# Power_supply.net
KiCad netlist of a schematic drawn in Altium Designer
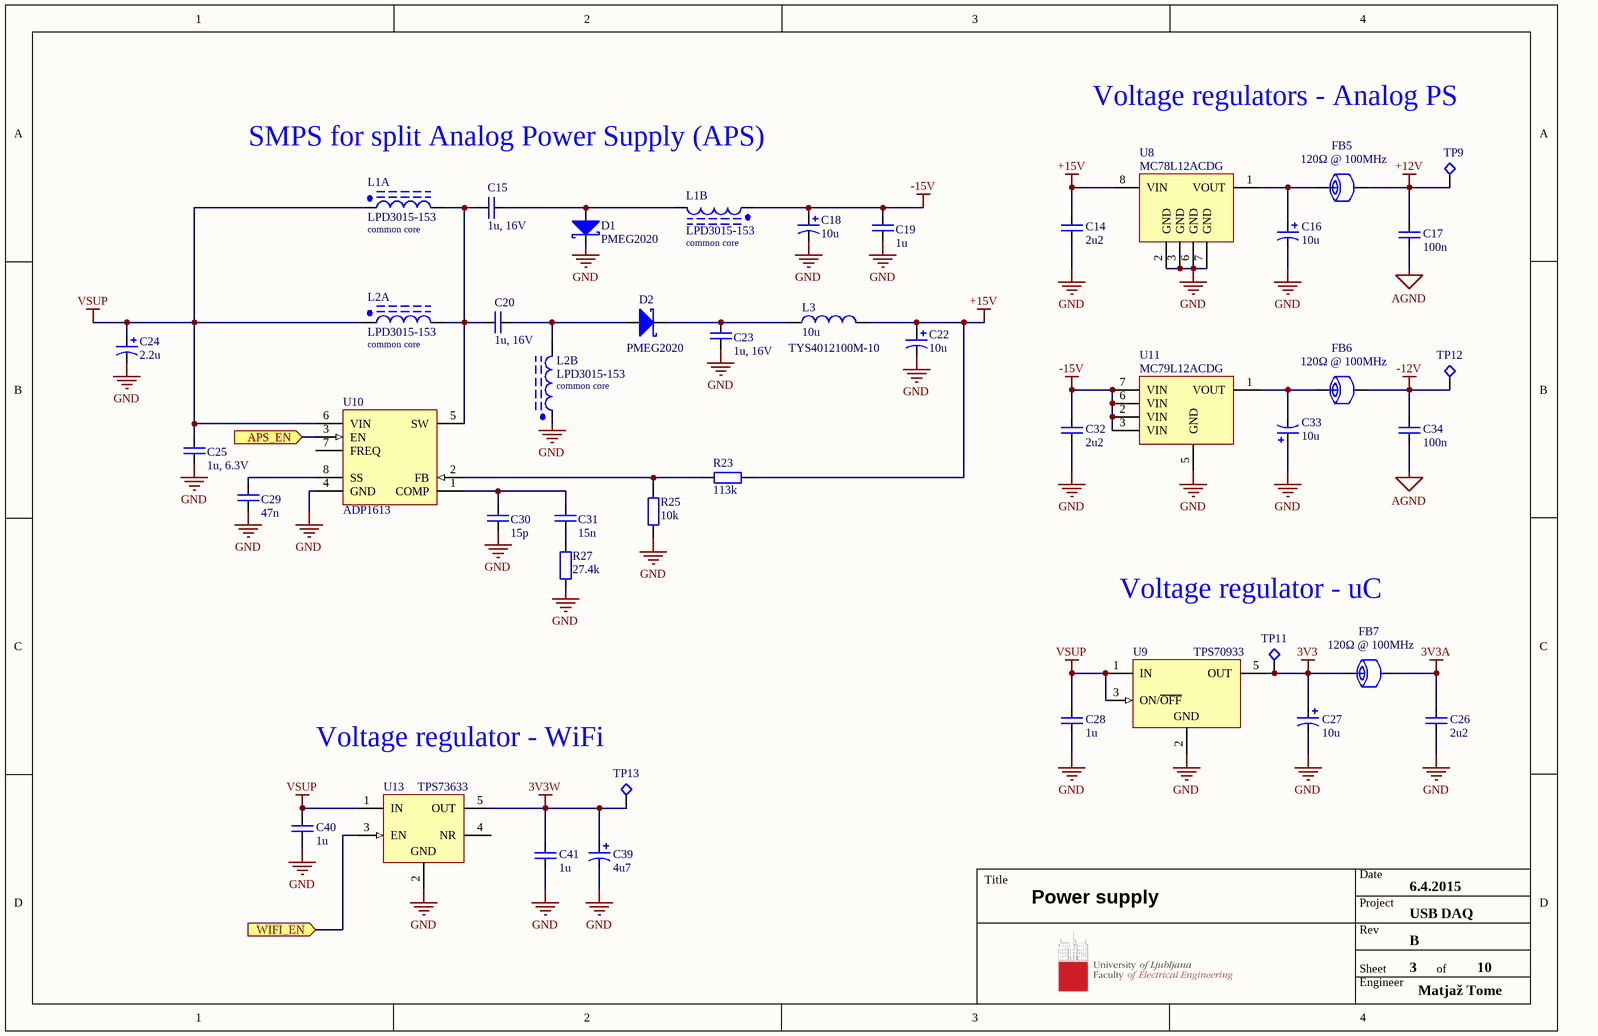
[diagram p0: Power_supply.SchDoc]

(export (version "E")
  (design (tool "Eeschema 10.0.6"))
  (components
    (comp (ref "C14")
      (value "2u2")
      (footprint "C_0603")
      (description "Generic capacitor")
      (fields (field (name "Comment") "comment"))
      (libsource (lib "DAQ") (part "Capacitor"))
    )
    (comp (ref "C15")
      (value "1u, 16V")
      (footprint "C_0603")
      (description "Generic capacitor")
      (fields (field (name "Comment") "comment"))
      (libsource (lib "DAQ") (part "Capacitor"))
    )
    (comp (ref "C16")
      (value "10u")
      (footprint "Tantalum Case A")
      (description "Generic polarized capacitor")
      (fields (field (name "Comment") "comment"))
      (libsource (lib "DAQ") (part "Capacitor - polarized"))
    )
    (comp (ref "C17")
      (value "100n")
      (footprint "C_0603")
      (description "Generic capacitor")
      (fields (field (name "Comment") "comment"))
      (libsource (lib "DAQ") (part "Capacitor"))
    )
    (comp (ref "C18")
      (value "10u")
      (footprint "Tantalum Case A")
      (description "Generic polarized capacitor")
      (fields (field (name "Comment") "comment"))
      (libsource (lib "") (part "Capacitor - polarized_1"))
    )
    (comp (ref "C19")
      (value "1u")
      (footprint "C_0603")
      (description "Generic capacitor")
      (fields (field (name "Comment") "comment"))
      (libsource (lib "DAQ") (part "Capacitor"))
    )
    (comp (ref "C20")
      (value "1u, 16V")
      (footprint "C_0603")
      (description "Generic capacitor")
      (fields (field (name "Comment") "comment"))
      (libsource (lib "DAQ") (part "Capacitor"))
    )
    (comp (ref "C22")
      (value "10u")
      (footprint "Tantalum Case A")
      (description "Generic polarized capacitor")
      (fields (field (name "Comment") "comment"))
      (libsource (lib "") (part "Capacitor - polarized_1"))
    )
    (comp (ref "C23")
      (value "1u, 16V")
      (footprint "C_0603")
      (description "Generic capacitor")
      (fields (field (name "Comment") "comment"))
      (libsource (lib "DAQ") (part "Capacitor"))
    )
    (comp (ref "C24")
      (value "2.2u")
      (footprint "Tantalum Case A")
      (description "Generic polarized capacitor")
      (fields (field (name "Comment") "comment"))
      (libsource (lib "") (part "Capacitor - polarized_1"))
    )
    (comp (ref "C25")
      (value "1u, 6.3V")
      (footprint "C_0603")
      (description "Generic capacitor")
      (fields (field (name "Comment") "comment"))
      (libsource (lib "DAQ") (part "Capacitor"))
    )
    (comp (ref "C26")
      (value "2u2")
      (footprint "C_0603")
      (description "Generic capacitor")
      (fields (field (name "Comment") "comment"))
      (libsource (lib "DAQ") (part "Capacitor"))
    )
    (comp (ref "C27")
      (value "10u")
      (footprint "Tantalum Case A")
      (description "Generic polarized capacitor")
      (fields (field (name "Comment") "comment"))
      (libsource (lib "DAQ") (part "Capacitor - polarized"))
    )
    (comp (ref "C28")
      (value "1u")
      (footprint "C_0603")
      (description "Generic capacitor")
      (fields (field (name "Comment") "comment"))
      (libsource (lib "DAQ") (part "Capacitor"))
    )
    (comp (ref "C29")
      (value "47n")
      (footprint "C_0603")
      (description "Generic capacitor")
      (fields (field (name "Comment") "comment"))
      (libsource (lib "DAQ") (part "Capacitor"))
    )
    (comp (ref "C30")
      (value "15p")
      (footprint "C_0603")
      (description "Generic capacitor")
      (fields (field (name "Comment") "comment"))
      (libsource (lib "DAQ") (part "Capacitor"))
    )
    (comp (ref "C31")
      (value "15n")
      (footprint "C_0603")
      (description "Generic capacitor")
      (fields (field (name "Comment") "comment"))
      (libsource (lib "DAQ") (part "Capacitor"))
    )
    (comp (ref "C32")
      (value "2u2")
      (footprint "C_0603")
      (description "Generic capacitor")
      (fields (field (name "Comment") "comment"))
      (libsource (lib "DAQ") (part "Capacitor"))
    )
    (comp (ref "C33")
      (value "10u")
      (footprint "Tantalum Case A")
      (description "Generic polarized capacitor")
      (fields (field (name "Comment") "comment"))
      (libsource (lib "DAQ") (part "Capacitor - polarized"))
    )
    (comp (ref "C34")
      (value "100n")
      (footprint "C_0603")
      (description "Generic capacitor")
      (fields (field (name "Comment") "comment"))
      (libsource (lib "DAQ") (part "Capacitor"))
    )
    (comp (ref "C39")
      (value "4u7")
      (footprint "Tantalum Case A")
      (description "Generic polarized capacitor")
      (fields (field (name "Comment") "comment"))
      (libsource (lib "DAQ") (part "Capacitor - polarized"))
    )
    (comp (ref "C40")
      (value "1u")
      (footprint "C_0603")
      (description "Generic capacitor")
      (fields (field (name "Comment") "comment"))
      (libsource (lib "DAQ") (part "Capacitor"))
    )
    (comp (ref "C41")
      (value "1u")
      (footprint "C_0603")
      (description "Generic capacitor")
      (fields (field (name "Comment") "comment"))
      (libsource (lib "DAQ") (part "Capacitor"))
    )
    (comp (ref "D1")
      (value "PMEG2020")
      (footprint "SOD323")
      (description "Schottky Rectifier, 20 V, 2 A, Single, SOD-323, 2 Pins, 525 mV")
      (fields (field (name "MANUFACTURER") "Infineon"))
      (libsource (lib "DAQ") (part "PMEG2020"))
    )
    (comp (ref "D2")
      (value "PMEG2020")
      (footprint "SOD323")
      (description "Schottky Rectifier, 20 V, 2 A, Single, SOD-323, 2 Pins, 525 mV")
      (fields (field (name "MANUFACTURER") "Infineon"))
      (libsource (lib "DAQ") (part "PMEG2020"))
    )
    (comp (ref "FB5")
      (value "120Ω @ 100MHz")
      (footprint "SMD_0805")
      (description "Ferrite Bead, 0805 [2012 Metric], 120 ohm, 800 mA, BLM21A Series, 0.15 ohm, ± 25%")
      (fields (field (name "MANUFACTURER") "Murata"))
      (libsource (lib "DAQ") (part "BLM21AG121SN1D"))
    )
    (comp (ref "FB6")
      (value "120Ω @ 100MHz")
      (footprint "SMD_0805")
      (description "Ferrite Bead, 0805 [2012 Metric], 120 ohm, 800 mA, BLM21A Series, 0.15 ohm, ± 25%")
      (fields (field (name "MANUFACTURER") "Murata"))
      (libsource (lib "DAQ") (part "BLM21AG121SN1D"))
    )
    (comp (ref "FB7")
      (value "120Ω @ 100MHz")
      (footprint "SMD_0805")
      (description "Ferrite Bead, 0805 [2012 Metric], 120 ohm, 800 mA, BLM21A Series, 0.15 ohm, ± 25%")
      (fields (field (name "MANUFACTURER") "Murata"))
      (libsource (lib "DAQ") (part "BLM21AG121SN1D"))
    )
    (comp (ref "L1")
      (value "LPD3015-153")
      (footprint "LPD3015")
      (description "Inductor, Coupled, 15 µH, 20%, 1.42 ohm, 460 mA, 3mm x 3mm x 1.4mm")
      (fields
        (field (name "MANUFACTURER") "Coilcraft")
        (field (name "TOLERANCE") "20%")
        (field (name "NOTE") "common core")
      )
      (libsource (lib "DAQ") (part "LPD3015-153"))
    )
    (comp (ref "L2")
      (value "LPD3015-153")
      (footprint "LPD3015")
      (description "Inductor, Coupled, 15 µH, 20%, 1.42 ohm, 460 mA, 3mm x 3mm x 1.4mm")
      (fields
        (field (name "MANUFACTURER") "Coilcraft")
        (field (name "TOLERANCE") "20%")
        (field (name "NOTE") "common core")
      )
      (libsource (lib "DAQ") (part "LPD3015-153"))
    )
    (comp (ref "L3")
      (value "10u")
      (footprint "IND_SMD_4X4mm")
      (description "Power Inductor (SMD), 10 µH, 770 mA, Shielded, 800 mA, TYS Series, 4mm x 4mm x 1.2mm")
      (fields
        (field (name "MANUFACTURER") "Laird Technologies")
        (field (name "TOLERANCE") "20%")
        (field (name "MANUFACTURER NUMBER") "TYS4012100M-10")
      )
      (libsource (lib "DAQ") (part "TYS4012100M-10"))
    )
    (comp (ref "R23")
      (value "113k")
      (footprint "R_0603")
      (description "Generic resistor")
      (fields (field (name "Comment") "comment"))
      (libsource (lib "DAQ") (part "Resistor"))
    )
    (comp (ref "R25")
      (value "10k")
      (footprint "R_0603")
      (description "Generic resistor")
      (fields (field (name "Comment") "comment"))
      (libsource (lib "DAQ") (part "Resistor"))
    )
    (comp (ref "R27")
      (value "27.4k")
      (footprint "R_0603")
      (description "Generic resistor")
      (fields (field (name "Comment") "comment"))
      (libsource (lib "DAQ") (part "Resistor"))
    )
    (comp (ref "TP9")
      (value "testpoint")
      (footprint "TP1_FULL")
      (description "testpoint 1.5mm diameter no hole")
      (fields (field (name "PART NUMBER") "XXC0006"))
      (libsource (lib "DAQ") (part "Test Point"))
    )
    (comp (ref "TP11")
      (value "testpoint")
      (footprint "TP1_FULL")
      (description "testpoint 1.5mm diameter no hole")
      (fields (field (name "PART NUMBER") "XXC0006"))
      (libsource (lib "DAQ") (part "Test Point"))
    )
    (comp (ref "TP12")
      (value "testpoint")
      (footprint "TP1_FULL")
      (description "testpoint 1.5mm diameter no hole")
      (fields (field (name "PART NUMBER") "XXC0006"))
      (libsource (lib "DAQ") (part "Test Point"))
    )
    (comp (ref "TP13")
      (value "testpoint")
      (footprint "TP1_FULL")
      (description "testpoint 1.5mm diameter no hole")
      (fields (field (name "PART NUMBER") "XXC0006"))
      (libsource (lib "DAQ") (part "Test Point"))
    )
    (comp (ref "U8")
      (value "MC78L12ACDG")
      (footprint "MC78L12ACDG")
      (description "Linear Voltage Regulator, 7812, Fixed, Positive, 19V To 35V In, 12V And 0.1A Out, SOIC-8")
      (fields (field (name "MANUFACTURER") "ON Semiconductors"))
      (libsource (lib "DAQ") (part "78LXX"))
    )
    (comp (ref "U9")
      (value "TPS70933")
      (footprint "SOT23-5")
      (description "1-µA IQ Voltage Regulators with Enable")
      (fields (field (name "PART NUMBER") "XLR0012") (field (name "MANUFACTURER") "Texas Instruments"))
      (libsource (lib "DAQ") (part "TPS709XX"))
    )
    (comp (ref "U10")
      (value "ADP1613")
      (footprint "MSOP8")
      (description "DC-DC Switching Boost, SEPIC Regulator, Adjustable, 2.5V-5.5Vin, 3.6V-20Vout, 2Aout, MSOP-8")
      (fields (field (name "MANUFACTURER") "Analog devices"))
      (libsource (lib "DAQ") (part "ADP161X"))
    )
    (comp (ref "U11")
      (value "MC79L12ACDG")
      (footprint "MC79L12ACDG")
      (description "Linear Voltage Regulator, 100 mA, 5 V, Negative Vout: -12 V; TJ = 0°C to +125°C")
      (fields (field (name "MANUFACTURER") "ON Semiconductors"))
      (libsource (lib "DAQ") (part "79LXX"))
    )
    (comp (ref "U13")
      (value "TPS73633")
      (footprint "SOT23-5")
      (description "Cap-Free, NMOS, 400-mA Low-Dropout Regulator with Reverse Current Protection")
      (fields (field (name "PART NUMBER") "XLR0013") (field (name "MANUFACTURER") "Texas instruments"))
      (libsource (lib "DAQ") (part "TPS736XX"))
    )
  )
  (nets
    (net (code "1") (name "+12V") (class "Default")
      (node (ref "C17") (pin "2") (pinfunction "2_2") (pintype "passive"))
      (node (ref "FB5") (pin "2") (pintype "passive"))
      (node (ref "TP9") (pin "1") (pinfunction "1_1") (pintype "passive"))
    )
    (net (code "2") (name "+15V") (class "Default")
      (node (ref "C14") (pin "1") (pinfunction "1_1") (pintype "passive"))
      (node (ref "C22") (pin "1") (pinfunction "1_1") (pintype "passive"))
      (node (ref "L3") (pin "2") (pinfunction "2_2") (pintype "passive"))
      (node (ref "R23") (pin "2") (pintype "passive"))
      (node (ref "U8") (pin "8") (pinfunction "VIN_8") (pintype "power_in"))
    )
    (net (code "3") (name "-12V") (class "Default")
      (node (ref "C34") (pin "2") (pinfunction "2_2") (pintype "passive"))
      (node (ref "FB6") (pin "2") (pintype "passive"))
      (node (ref "TP12") (pin "1") (pinfunction "1_1") (pintype "passive"))
    )
    (net (code "4") (name "-15V") (class "Default")
      (node (ref "C18") (pin "1") (pinfunction "1_1") (pintype "passive"))
      (node (ref "C19") (pin "1") (pinfunction "1_1") (pintype "passive"))
      (node (ref "C32") (pin "1") (pinfunction "1_1") (pintype "passive"))
      (node (ref "L1") (pin "4") (pinfunction "4_4") (pintype "passive"))
      (node (ref "U11") (pin "2") (pinfunction "VIN_2") (pintype "power_in"))
      (node (ref "U11") (pin "3") (pinfunction "VIN_3") (pintype "power_in"))
      (node (ref "U11") (pin "6") (pinfunction "VIN_6") (pintype "power_in"))
      (node (ref "U11") (pin "7") (pinfunction "VIN_7") (pintype "power_in"))
    )
    (net (code "5") (name "/APS_EN") (class "Default")
      (node (ref "U10") (pin "3") (pinfunction "EN_3") (pintype "input"))
    )
    (net (code "6") (name "/WIFI_EN") (class "Default")
      (node (ref "U13") (pin "3") (pinfunction "EN_3") (pintype "input"))
    )
    (net (code "7") (name "3V3") (class "Default")
      (node (ref "C27") (pin "1") (pinfunction "1_1") (pintype "passive"))
      (node (ref "FB7") (pin "1") (pintype "passive"))
      (node (ref "TP11") (pin "1") (pinfunction "1_1") (pintype "passive"))
      (node (ref "U9") (pin "5") (pinfunction "OUT_5") (pintype "power_in"))
    )
    (net (code "8") (name "3V3A") (class "Default")
      (node (ref "C26") (pin "1") (pinfunction "1_1") (pintype "passive"))
      (node (ref "FB7") (pin "2") (pintype "passive"))
    )
    (net (code "9") (name "3V3W") (class "Default")
      (node (ref "C39") (pin "1") (pinfunction "1_1") (pintype "passive"))
      (node (ref "C41") (pin "1") (pinfunction "1_1") (pintype "passive"))
      (node (ref "TP13") (pin "1") (pinfunction "1_1") (pintype "passive"))
      (node (ref "U13") (pin "5") (pinfunction "OUT_5") (pintype "power_in"))
    )
    (net (code "10") (name "AGND") (class "Default")
      (node (ref "C17") (pin "1") (pinfunction "1_1") (pintype "passive"))
      (node (ref "C34") (pin "1") (pinfunction "1_1") (pintype "passive"))
    )
    (net (code "11") (name "GND") (class "Default")
      (node (ref "C14") (pin "2") (pinfunction "2_2") (pintype "passive"))
      (node (ref "C16") (pin "2") (pinfunction "2_2") (pintype "passive"))
      (node (ref "C18") (pin "2") (pinfunction "2_2") (pintype "passive"))
      (node (ref "C19") (pin "2") (pinfunction "2_2") (pintype "passive"))
      (node (ref "C22") (pin "2") (pinfunction "2_2") (pintype "passive"))
      (node (ref "C23") (pin "2") (pinfunction "2_2") (pintype "passive"))
      (node (ref "C24") (pin "2") (pinfunction "2_2") (pintype "passive"))
      (node (ref "C25") (pin "1") (pinfunction "1_1") (pintype "passive"))
      (node (ref "C26") (pin "2") (pinfunction "2_2") (pintype "passive"))
      (node (ref "C27") (pin "2") (pinfunction "2_2") (pintype "passive"))
      (node (ref "C28") (pin "2") (pinfunction "2_2") (pintype "passive"))
      (node (ref "C29") (pin "2") (pinfunction "2_2") (pintype "passive"))
      (node (ref "C30") (pin "1") (pinfunction "1_1") (pintype "passive"))
      (node (ref "C32") (pin "2") (pinfunction "2_2") (pintype "passive"))
      (node (ref "C33") (pin "1") (pinfunction "1_1") (pintype "passive"))
      (node (ref "C39") (pin "2") (pinfunction "2_2") (pintype "passive"))
      (node (ref "C40") (pin "2") (pinfunction "2_2") (pintype "passive"))
      (node (ref "C41") (pin "2") (pinfunction "2_2") (pintype "passive"))
      (node (ref "D1") (pin "2") (pinfunction "K_2") (pintype "passive"))
      (node (ref "L2") (pin "4") (pinfunction "4_4") (pintype "passive"))
      (node (ref "R25") (pin "2") (pintype "passive"))
      (node (ref "R27") (pin "1") (pintype "passive"))
      (node (ref "U10") (pin "4") (pinfunction "GND_4") (pintype "power_in"))
      (node (ref "U11") (pin "5") (pinfunction "GND_5") (pintype "power_in"))
      (node (ref "U13") (pin "2") (pinfunction "GND_2") (pintype "power_in"))
      (node (ref "U8") (pin "2") (pinfunction "GND_2") (pintype "power_in"))
      (node (ref "U8") (pin "3") (pinfunction "GND_3") (pintype "power_in"))
      (node (ref "U8") (pin "6") (pinfunction "GND_6") (pintype "power_in"))
      (node (ref "U8") (pin "7") (pinfunction "GND_7") (pintype "power_in"))
      (node (ref "U9") (pin "2") (pinfunction "GND_2") (pintype "power_in"))
    )
    (net (code "12") (name "Net-(C31-Pad1)") (class "Default")
      (node (ref "C31") (pin "1") (pinfunction "1_1") (pintype "passive"))
      (node (ref "R27") (pin "2") (pintype "passive"))
    )
    (net (code "13") (name "Net-(D1-A)") (class "Default")
      (node (ref "C15") (pin "1") (pinfunction "1_1") (pintype "passive"))
      (node (ref "D1") (pin "1") (pinfunction "A_1") (pintype "passive"))
      (node (ref "L1") (pin "3") (pinfunction "3_3") (pintype "passive"))
    )
    (net (code "14") (name "Net-(D2-A)") (class "Default")
      (node (ref "C20") (pin "2") (pinfunction "2_2") (pintype "passive"))
      (node (ref "D2") (pin "1") (pinfunction "A_1") (pintype "passive"))
      (node (ref "L2") (pin "3") (pinfunction "3_3") (pintype "passive"))
    )
    (net (code "15") (name "Net-(D2-K)") (class "Default")
      (node (ref "C23") (pin "1") (pinfunction "1_1") (pintype "passive"))
      (node (ref "D2") (pin "2") (pinfunction "K_2") (pintype "passive"))
      (node (ref "L3") (pin "1") (pinfunction "1_1") (pintype "passive"))
    )
    (net (code "16") (name "Net-(U8-VOUT)") (class "Default")
      (node (ref "C16") (pin "1") (pinfunction "1_1") (pintype "passive"))
      (node (ref "FB5") (pin "1") (pintype "passive"))
      (node (ref "U8") (pin "1") (pinfunction "VOUT_1") (pintype "power_in"))
    )
    (net (code "17") (name "Net-(U10-COMP)") (class "Default")
      (node (ref "C30") (pin "2") (pinfunction "2_2") (pintype "passive"))
      (node (ref "C31") (pin "2") (pinfunction "2_2") (pintype "passive"))
      (node (ref "U10") (pin "1") (pinfunction "COMP_1") (pintype "passive"))
    )
    (net (code "18") (name "Net-(U10-FB)") (class "Default")
      (node (ref "R23") (pin "1") (pintype "passive"))
      (node (ref "R25") (pin "1") (pintype "passive"))
      (node (ref "U10") (pin "2") (pinfunction "FB_2") (pintype "input"))
    )
    (net (code "19") (name "Net-(U10-SS)") (class "Default")
      (node (ref "C29") (pin "1") (pinfunction "1_1") (pintype "passive"))
      (node (ref "U10") (pin "8") (pinfunction "SS_8") (pintype "passive"))
    )
    (net (code "20") (name "Net-(U10-SW)") (class "Default")
      (node (ref "C15") (pin "2") (pinfunction "2_2") (pintype "passive"))
      (node (ref "C20") (pin "1") (pinfunction "1_1") (pintype "passive"))
      (node (ref "L1") (pin "2") (pinfunction "2_2") (pintype "passive"))
      (node (ref "L2") (pin "2") (pinfunction "2_2") (pintype "passive"))
      (node (ref "U10") (pin "5") (pinfunction "SW_5") (pintype "passive"))
    )
    (net (code "21") (name "Net-(U11-VOUT)") (class "Default")
      (node (ref "C33") (pin "2") (pinfunction "2_2") (pintype "passive"))
      (node (ref "FB6") (pin "1") (pintype "passive"))
      (node (ref "U11") (pin "1") (pinfunction "VOUT_1") (pintype "power_in"))
    )
    (net (code "22") (name "VSUP") (class "Default")
      (node (ref "C24") (pin "1") (pinfunction "1_1") (pintype "passive"))
      (node (ref "C25") (pin "2") (pinfunction "2_2") (pintype "passive"))
      (node (ref "C28") (pin "1") (pinfunction "1_1") (pintype "passive"))
      (node (ref "C40") (pin "1") (pinfunction "1_1") (pintype "passive"))
      (node (ref "L1") (pin "1") (pinfunction "1_1") (pintype "passive"))
      (node (ref "L2") (pin "1") (pinfunction "1_1") (pintype "passive"))
      (node (ref "U10") (pin "6") (pinfunction "VIN_6") (pintype "power_in"))
      (node (ref "U13") (pin "1") (pinfunction "IN_1") (pintype "power_in"))
      (node (ref "U9") (pin "1") (pinfunction "IN_1") (pintype "power_in"))
      (node (ref "U9") (pin "3") (pinfunction "ON/~{OFF}_3") (pintype "input"))
    )
    (net (code "23") (name "unconnected-(U10-FREQ-Pad7)") (class "Default")
      (node (ref "U10") (pin "7") (pinfunction "FREQ_7") (pintype "passive"))
    )
    (net (code "24") (name "unconnected-(U13-NR-Pad4)") (class "Default")
      (node (ref "U13") (pin "4") (pinfunction "NR_4") (pintype "passive"))
    )
  )
)
